# MAPE-CUN-Large-022-Input.net
KiCad netlist of a schematic drawn in EAGLE
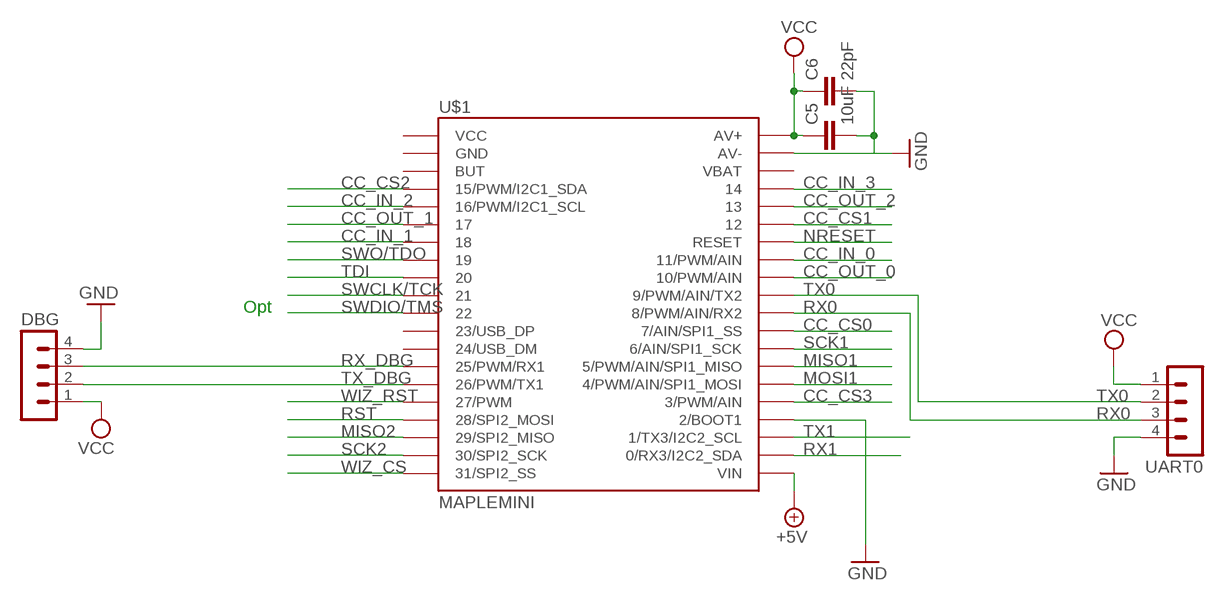
[diagram p0: schematic, sheet 1]

(export (version "E")
  (design (tool "Eeschema 10.0.6"))
  (components
    (comp (ref "C5")
      (value "10uF")
      (footprint "eagle-import:C1210")
      (libsource (lib "eagle-import") (part "C-EUC1210"))
    )
    (comp (ref "C6")
      (value "22pF")
      (footprint "eagle-import:C0805")
      (libsource (lib "eagle-import") (part "C-EUC0805"))
    )
    (comp (ref "DBG")
      (value "MA04-1")
      (footprint "eagle-import:MA04-1")
      (libsource (lib "eagle-import") (part "MA04-1"))
    )
    (comp (ref "U$1")
      (value "MAPLEMINI")
      (footprint "eagle-import:20-DIP")
      (libsource (lib "eagle-import") (part "MAPLEMINI"))
    )
    (comp (ref "UART0")
      (value "MA04-1")
      (footprint "eagle-import:MA04-1")
      (libsource (lib "eagle-import") (part "MA04-1"))
    )
  )
  (nets
    (net (code "1") (name "+5V") (class "Default")
      (node (ref "U$1") (pin "21") (pinfunction "VIN_21") (pintype "bidirectional"))
    )
    (net (code "2") (name "/CC_CS0") (class "Default")
      (node (ref "U$1") (pin "29") (pinfunction "7/AIN/SPI1_SS_29") (pintype "bidirectional"))
    )
    (net (code "3") (name "/CC_CS1") (class "Default")
      (node (ref "U$1") (pin "35") (pinfunction "12_35") (pintype "bidirectional"))
    )
    (net (code "4") (name "/CC_CS2") (class "Default")
      (node (ref "U$1") (pin "4") (pinfunction "15/PWM/I2C1_SDA_4") (pintype "bidirectional"))
    )
    (net (code "5") (name "/CC_CS3") (class "Default")
      (node (ref "U$1") (pin "25") (pinfunction "3/PWM/AIN_25") (pintype "bidirectional"))
    )
    (net (code "6") (name "/CC_IN_0") (class "Default")
      (node (ref "U$1") (pin "33") (pinfunction "11/PWM/AIN_33") (pintype "bidirectional"))
    )
    (net (code "7") (name "/CC_IN_1") (class "Default")
      (node (ref "U$1") (pin "7") (pinfunction "18_7") (pintype "bidirectional"))
    )
    (net (code "8") (name "/CC_IN_2") (class "Default")
      (node (ref "U$1") (pin "5") (pinfunction "16/PWM/I2C1_SCL_5") (pintype "bidirectional"))
    )
    (net (code "9") (name "/CC_IN_3") (class "Default")
      (node (ref "U$1") (pin "37") (pinfunction "14_37") (pintype "bidirectional"))
    )
    (net (code "10") (name "/CC_OUT_0") (class "Default")
      (node (ref "U$1") (pin "32") (pinfunction "10/PWM/AIN_32") (pintype "bidirectional"))
    )
    (net (code "11") (name "/CC_OUT_1") (class "Default")
      (node (ref "U$1") (pin "6") (pinfunction "17_6") (pintype "bidirectional"))
    )
    (net (code "12") (name "/CC_OUT_2") (class "Default")
      (node (ref "U$1") (pin "36") (pinfunction "13_36") (pintype "bidirectional"))
    )
    (net (code "13") (name "/MISO1") (class "Default")
      (node (ref "U$1") (pin "27") (pinfunction "5/PWM/AIN/SPI1_MISO_27") (pintype "bidirectional"))
    )
    (net (code "14") (name "/MISO2") (class "Default")
      (node (ref "U$1") (pin "18") (pinfunction "29/SPI2_MISO_18") (pintype "bidirectional"))
    )
    (net (code "15") (name "/MOSI1") (class "Default")
      (node (ref "U$1") (pin "26") (pinfunction "4/PWM/AIN/SPI1_MOSI_26") (pintype "bidirectional"))
    )
    (net (code "16") (name "/NRESET") (class "Default")
      (node (ref "U$1") (pin "34") (pinfunction "RESET_34") (pintype "bidirectional"))
    )
    (net (code "17") (name "/RST") (class "Default")
      (node (ref "U$1") (pin "17") (pinfunction "28/SPI2_MOSI_17") (pintype "bidirectional"))
    )
    (net (code "18") (name "/RX0") (class "Default")
      (node (ref "U$1") (pin "30") (pinfunction "8/PWM/AIN/RX2_30") (pintype "bidirectional"))
      (node (ref "UART0") (pin "3") (pinfunction "3_3") (pintype "passive"))
    )
    (net (code "19") (name "/RX1") (class "Default")
      (node (ref "U$1") (pin "22") (pinfunction "0/RX3/I2C2_SDA_22") (pintype "bidirectional"))
    )
    (net (code "20") (name "/RX_DBG") (class "Default")
      (node (ref "DBG") (pin "3") (pinfunction "3_3") (pintype "passive"))
      (node (ref "U$1") (pin "14") (pinfunction "25/PWM/RX1_14") (pintype "bidirectional"))
    )
    (net (code "21") (name "/SCK1") (class "Default")
      (node (ref "U$1") (pin "28") (pinfunction "6/AIN/SPI1_SCK_28") (pintype "bidirectional"))
    )
    (net (code "22") (name "/SCK2") (class "Default")
      (node (ref "U$1") (pin "19") (pinfunction "30/SPI2_SCK_19") (pintype "bidirectional"))
    )
    (net (code "23") (name "/SWCLK{slash}TCK") (class "Default")
      (node (ref "U$1") (pin "10") (pinfunction "21_10") (pintype "bidirectional"))
    )
    (net (code "24") (name "/SWDIO{slash}TMS") (class "Default")
      (node (ref "U$1") (pin "11") (pinfunction "22_11") (pintype "bidirectional"))
    )
    (net (code "25") (name "/SWO{slash}TDO") (class "Default")
      (node (ref "U$1") (pin "8") (pinfunction "19_8") (pintype "bidirectional"))
    )
    (net (code "26") (name "/TDI") (class "Default")
      (node (ref "U$1") (pin "9") (pinfunction "20_9") (pintype "bidirectional"))
    )
    (net (code "27") (name "/TX0") (class "Default")
      (node (ref "U$1") (pin "31") (pinfunction "9/PWM/AIN/TX2_31") (pintype "bidirectional"))
      (node (ref "UART0") (pin "2") (pinfunction "2_2") (pintype "passive"))
    )
    (net (code "28") (name "/TX1") (class "Default")
      (node (ref "U$1") (pin "23") (pinfunction "1/TX3/I2C2_SCL_23") (pintype "bidirectional"))
    )
    (net (code "29") (name "/TX_DBG") (class "Default")
      (node (ref "DBG") (pin "2") (pinfunction "2_2") (pintype "passive"))
      (node (ref "U$1") (pin "15") (pinfunction "26/PWM/TX1_15") (pintype "bidirectional"))
    )
    (net (code "30") (name "/WIZ_CS") (class "Default")
      (node (ref "U$1") (pin "20") (pinfunction "31/SPI2_SS_20") (pintype "bidirectional"))
    )
    (net (code "31") (name "/WIZ_RST") (class "Default")
      (node (ref "U$1") (pin "16") (pinfunction "27/PWM_16") (pintype "bidirectional"))
    )
    (net (code "32") (name "GND") (class "Default")
      (node (ref "C5") (pin "2") (pinfunction "2_2") (pintype "passive"))
      (node (ref "C6") (pin "2") (pinfunction "2_2") (pintype "passive"))
      (node (ref "DBG") (pin "4") (pinfunction "4_4") (pintype "passive"))
      (node (ref "U$1") (pin "24") (pinfunction "2/BOOT1_24") (pintype "bidirectional"))
      (node (ref "U$1") (pin "39") (pinfunction "AV-_39") (pintype "bidirectional"))
      (node (ref "UART0") (pin "4") (pinfunction "4_4") (pintype "passive"))
    )
    (net (code "33") (name "VCC") (class "Default")
      (node (ref "C5") (pin "1") (pinfunction "1_1") (pintype "passive"))
      (node (ref "C6") (pin "1") (pinfunction "1_1") (pintype "passive"))
      (node (ref "DBG") (pin "1") (pinfunction "1_1") (pintype "passive"))
      (node (ref "U$1") (pin "40") (pinfunction "AV+_40") (pintype "bidirectional"))
      (node (ref "UART0") (pin "1") (pinfunction "1_1") (pintype "passive"))
    )
    (net (code "34") (name "unconnected-(U$1-23{slash}USB_DP-Pad12)") (class "Default")
      (node (ref "U$1") (pin "12") (pinfunction "23/USB_DP_12") (pintype "bidirectional"))
    )
    (net (code "35") (name "unconnected-(U$1-24{slash}USB_DM-Pad13)") (class "Default")
      (node (ref "U$1") (pin "13") (pinfunction "24/USB_DM_13") (pintype "bidirectional"))
    )
    (net (code "36") (name "unconnected-(U$1-BUT-Pad3)") (class "Default")
      (node (ref "U$1") (pin "3") (pinfunction "BUT_3") (pintype "bidirectional"))
    )
    (net (code "37") (name "unconnected-(U$1-GND-Pad2)") (class "Default")
      (node (ref "U$1") (pin "2") (pinfunction "GND_2") (pintype "bidirectional"))
    )
    (net (code "38") (name "unconnected-(U$1-VBAT-Pad38)") (class "Default")
      (node (ref "U$1") (pin "38") (pinfunction "VBAT_38") (pintype "bidirectional"))
    )
    (net (code "39") (name "unconnected-(U$1-VCC-Pad1)") (class "Default")
      (node (ref "U$1") (pin "1") (pinfunction "VCC_1") (pintype "bidirectional"))
    )
  )
)
